# STC11F04E_SOP20_UTo24G.net
KiCad netlist of a schematic drawn in Altium Designer
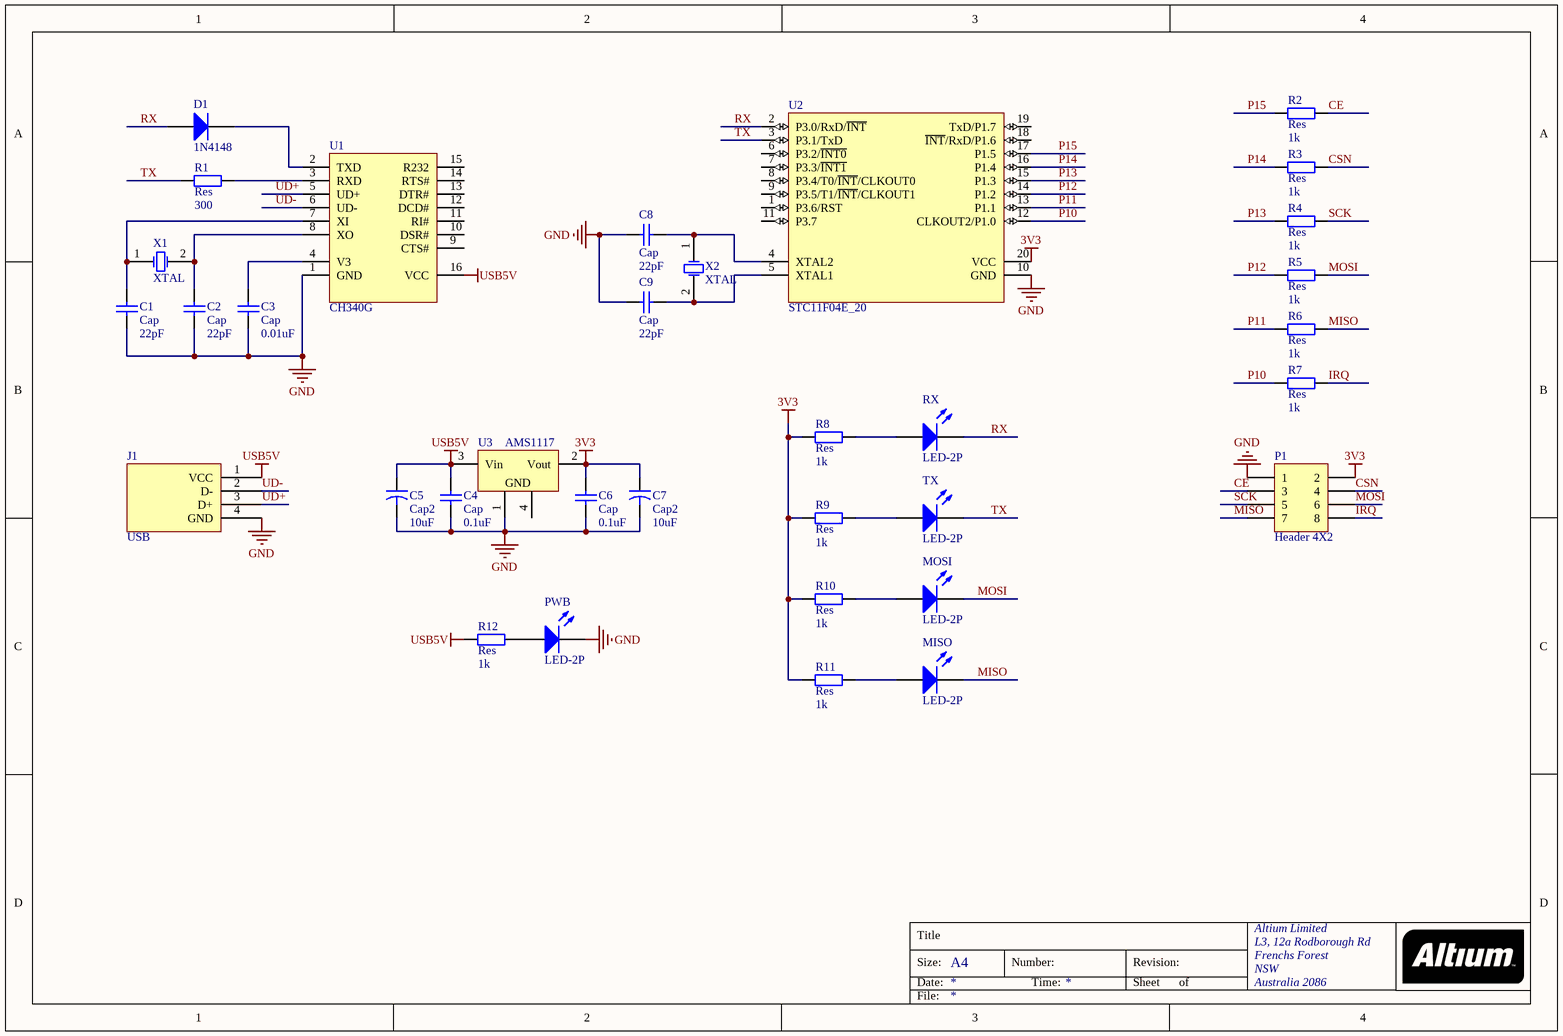
[diagram p0: STC11F04E_SOP20_UTo24G.SchDoc]

(export (version "E")
  (design (tool "Eeschema 10.0.6"))
  (components
    (comp (ref "C1")
      (value "Cap")
      (footprint "C0805")
      (description "Capacitor")
      (fields (field (name "ALTIUM_VALUE") "22pF") (field (name "PUBLISHER") "Altium Limited"))
      (libsource (lib "Devices") (part "Cap"))
    )
    (comp (ref "C2")
      (value "Cap")
      (footprint "C0805")
      (description "Capacitor")
      (fields (field (name "ALTIUM_VALUE") "22pF") (field (name "PUBLISHER") "Altium Limited"))
      (libsource (lib "Devices") (part "Cap"))
    )
    (comp (ref "C3")
      (value "Cap")
      (footprint "C0805")
      (description "Capacitor")
      (fields (field (name "ALTIUM_VALUE") "0.01uF") (field (name "PUBLISHER") "Altium Limited"))
      (libsource (lib "Devices") (part "Cap"))
    )
    (comp (ref "C4")
      (value "Cap")
      (footprint "C0805")
      (description "Capacitor")
      (fields (field (name "ALTIUM_VALUE") "0.1uF") (field (name "PUBLISHER") "Altium Limited"))
      (libsource (lib "Devices") (part "Cap"))
    )
    (comp (ref "C5")
      (value "Cap2")
      (footprint "C1206A")
      (description "Capacitor")
      (fields (field (name "ALTIUM_VALUE") "10uF") (field (name "PUBLISHER") "Altium Limited"))
      (libsource (lib "Devices") (part "Cap2"))
    )
    (comp (ref "C6")
      (value "Cap")
      (footprint "C0805")
      (description "Capacitor")
      (fields (field (name "ALTIUM_VALUE") "0.1uF") (field (name "PUBLISHER") "Altium Limited"))
      (libsource (lib "Devices") (part "Cap"))
    )
    (comp (ref "C7")
      (value "Cap2")
      (footprint "C1206A")
      (description "Capacitor")
      (fields (field (name "ALTIUM_VALUE") "10uF") (field (name "PUBLISHER") "Altium Limited"))
      (libsource (lib "Devices") (part "Cap2"))
    )
    (comp (ref "C8")
      (value "Cap")
      (footprint "C0805")
      (description "Capacitor")
      (fields (field (name "ALTIUM_VALUE") "22pF") (field (name "PUBLISHER") "Altium Limited"))
      (libsource (lib "Devices") (part "Cap"))
    )
    (comp (ref "C9")
      (value "Cap")
      (footprint "C0805")
      (description "Capacitor")
      (fields (field (name "ALTIUM_VALUE") "22pF") (field (name "PUBLISHER") "Altium Limited"))
      (libsource (lib "Devices") (part "Cap"))
    )
    (comp (ref "D1")
      (value "1N4148")
      (footprint "C1206A")
      (description "快速开关二极管")
      (libsource (lib "Devices") (part "1N4148"))
    )
    (comp (ref "J1")
      (value "USB")
      (footprint "USB-A-G")
      (description "USB-B")
      (libsource (lib "Connectors") (part "USB"))
    )
    (comp (ref "MISO")
      (value "LED-2P")
      (footprint "C0805")
      (description "发光二极管")
      (libsource (lib "Devices") (part "LED-2P"))
    )
    (comp (ref "MOSI")
      (value "LED-2P")
      (footprint "C0805")
      (description "发光二极管")
      (libsource (lib "Devices") (part "LED-2P"))
    )
    (comp (ref "P1")
      (value "Header 4X2")
      (footprint "HDR2X4")
      (description "Header, 4-Pin, Dual row")
      (fields (field (name "PUBLISHER") "Altium Limited"))
      (libsource (lib "Connectors") (part "Header 4X2"))
    )
    (comp (ref "PWB")
      (value "LED-2P")
      (footprint "C0805")
      (description "发光二极管")
      (libsource (lib "Devices") (part "LED-2P"))
    )
    (comp (ref "R1")
      (value "Res")
      (footprint "0805")
      (description "Resistor")
      (fields (field (name "ALTIUM_VALUE") "300") (field (name "PUBLISHER") "Altium Limited"))
      (libsource (lib "Devices") (part "Res"))
    )
    (comp (ref "R2")
      (value "Res")
      (footprint "0805")
      (description "Resistor")
      (fields (field (name "ALTIUM_VALUE") "1k") (field (name "PUBLISHER") "Altium Limited"))
      (libsource (lib "Devices") (part "Res"))
    )
    (comp (ref "R3")
      (value "Res")
      (footprint "0805")
      (description "Resistor")
      (fields (field (name "ALTIUM_VALUE") "1k") (field (name "PUBLISHER") "Altium Limited"))
      (libsource (lib "Devices") (part "Res"))
    )
    (comp (ref "R4")
      (value "Res")
      (footprint "0805")
      (description "Resistor")
      (fields (field (name "ALTIUM_VALUE") "1k") (field (name "PUBLISHER") "Altium Limited"))
      (libsource (lib "Devices") (part "Res"))
    )
    (comp (ref "R5")
      (value "Res")
      (footprint "0805")
      (description "Resistor")
      (fields (field (name "ALTIUM_VALUE") "1k") (field (name "PUBLISHER") "Altium Limited"))
      (libsource (lib "Devices") (part "Res"))
    )
    (comp (ref "R6")
      (value "Res")
      (footprint "0805")
      (description "Resistor")
      (fields (field (name "ALTIUM_VALUE") "1k") (field (name "PUBLISHER") "Altium Limited"))
      (libsource (lib "Devices") (part "Res"))
    )
    (comp (ref "R7")
      (value "Res")
      (footprint "0805")
      (description "Resistor")
      (fields (field (name "ALTIUM_VALUE") "1k") (field (name "PUBLISHER") "Altium Limited"))
      (libsource (lib "Devices") (part "Res"))
    )
    (comp (ref "R8")
      (value "Res")
      (footprint "0805")
      (description "Resistor")
      (fields (field (name "ALTIUM_VALUE") "1k") (field (name "PUBLISHER") "Altium Limited"))
      (libsource (lib "Devices") (part "Res"))
    )
    (comp (ref "R9")
      (value "Res")
      (footprint "0805")
      (description "Resistor")
      (fields (field (name "ALTIUM_VALUE") "1k") (field (name "PUBLISHER") "Altium Limited"))
      (libsource (lib "Devices") (part "Res"))
    )
    (comp (ref "R10")
      (value "Res")
      (footprint "0805")
      (description "Resistor")
      (fields (field (name "ALTIUM_VALUE") "1k") (field (name "PUBLISHER") "Altium Limited"))
      (libsource (lib "Devices") (part "Res"))
    )
    (comp (ref "R11")
      (value "Res")
      (footprint "0805")
      (description "Resistor")
      (fields (field (name "ALTIUM_VALUE") "1k") (field (name "PUBLISHER") "Altium Limited"))
      (libsource (lib "Devices") (part "Res"))
    )
    (comp (ref "R12")
      (value "Res")
      (footprint "0805")
      (description "Resistor")
      (fields (field (name "ALTIUM_VALUE") "1k") (field (name "PUBLISHER") "Altium Limited"))
      (libsource (lib "Devices") (part "Res"))
    )
    (comp (ref "RX")
      (value "LED-2P")
      (footprint "C0805")
      (description "发光二极管")
      (libsource (lib "Devices") (part "LED-2P"))
    )
    (comp (ref "TX")
      (value "LED-2P")
      (footprint "C0805")
      (description "发光二极管")
      (libsource (lib "Devices") (part "LED-2P"))
    )
    (comp (ref "U1")
      (value "CH340G")
      (footprint "SOP16")
      (description "USB 总线转接芯片")
      (libsource (lib "IC") (part "CH340G"))
    )
    (comp (ref "U2")
      (value "STC11F04E_20")
      (footprint "SOP20")
      (description "增强型8051单片机")
      (libsource (lib "STC") (part "STC11F04E_20"))
    )
    (comp (ref "U3")
      (value "AMS1117")
      (footprint "SOT-223")
      (description "低压稳压器-1A")
      (libsource (lib "IC") (part "AMS1117"))
    )
    (comp (ref "X1")
      (value "XTAL")
      (footprint "XTAL1")
      (description "Crystal Oscillator")
      (fields (field (name "PUBLISHER") "Altium Limited"))
      (libsource (lib "Miscellaneous Devices") (part "XTAL"))
    )
    (comp (ref "X2")
      (value "XTAL")
      (footprint "XTAL1")
      (description "Crystal Oscillator")
      (fields (field (name "PUBLISHER") "Altium Limited"))
      (libsource (lib "Miscellaneous Devices") (part "XTAL"))
    )
  )
  (nets
    (net (code "1") (name "/CE") (class "Default")
      (node (ref "P1") (pin "3") (pinfunction "3_3") (pintype "passive"))
      (node (ref "R2") (pin "2") (pinfunction "2_2") (pintype "passive"))
    )
    (net (code "2") (name "/CSN") (class "Default")
      (node (ref "P1") (pin "4") (pinfunction "4_4") (pintype "passive"))
      (node (ref "R3") (pin "2") (pinfunction "2_2") (pintype "passive"))
    )
    (net (code "3") (name "/IRQ") (class "Default")
      (node (ref "P1") (pin "8") (pinfunction "8_8") (pintype "passive"))
      (node (ref "R7") (pin "2") (pinfunction "2_2") (pintype "passive"))
    )
    (net (code "4") (name "/MISO") (class "Default")
      (node (ref "MISO") (pin "2") (pinfunction "K_2") (pintype "passive"))
      (node (ref "P1") (pin "7") (pinfunction "7_7") (pintype "passive"))
      (node (ref "R6") (pin "2") (pinfunction "2_2") (pintype "passive"))
    )
    (net (code "5") (name "/MOSI") (class "Default")
      (node (ref "MOSI") (pin "2") (pinfunction "K_2") (pintype "passive"))
      (node (ref "P1") (pin "6") (pinfunction "6_6") (pintype "passive"))
      (node (ref "R5") (pin "2") (pinfunction "2_2") (pintype "passive"))
    )
    (net (code "6") (name "/P10") (class "Default")
      (node (ref "R7") (pin "1") (pinfunction "1_1") (pintype "passive"))
      (node (ref "U2") (pin "12") (pinfunction "CLKOUT2/P1.0_12") (pintype "bidirectional"))
    )
    (net (code "7") (name "/P11") (class "Default")
      (node (ref "R6") (pin "1") (pinfunction "1_1") (pintype "passive"))
      (node (ref "U2") (pin "13") (pinfunction "P1.1_13") (pintype "bidirectional"))
    )
    (net (code "8") (name "/P12") (class "Default")
      (node (ref "R5") (pin "1") (pinfunction "1_1") (pintype "passive"))
      (node (ref "U2") (pin "14") (pinfunction "P1.2_14") (pintype "bidirectional"))
    )
    (net (code "9") (name "/P13") (class "Default")
      (node (ref "R4") (pin "1") (pinfunction "1_1") (pintype "passive"))
      (node (ref "U2") (pin "15") (pinfunction "P1.3_15") (pintype "bidirectional"))
    )
    (net (code "10") (name "/P14") (class "Default")
      (node (ref "R3") (pin "1") (pinfunction "1_1") (pintype "passive"))
      (node (ref "U2") (pin "16") (pinfunction "P1.4_16") (pintype "bidirectional"))
    )
    (net (code "11") (name "/P15") (class "Default")
      (node (ref "R2") (pin "1") (pinfunction "1_1") (pintype "passive"))
      (node (ref "U2") (pin "17") (pinfunction "P1.5_17") (pintype "bidirectional"))
    )
    (net (code "12") (name "/RX") (class "Default")
      (node (ref "D1") (pin "1") (pinfunction "A_1") (pintype "passive"))
      (node (ref "RX") (pin "2") (pinfunction "K_2") (pintype "passive"))
      (node (ref "U2") (pin "2") (pinfunction "P3.0/RxD/~{INT}_2") (pintype "bidirectional"))
    )
    (net (code "13") (name "/SCK") (class "Default")
      (node (ref "P1") (pin "5") (pinfunction "5_5") (pintype "passive"))
      (node (ref "R4") (pin "2") (pinfunction "2_2") (pintype "passive"))
    )
    (net (code "14") (name "/TX") (class "Default")
      (node (ref "R1") (pin "1") (pinfunction "1_1") (pintype "passive"))
      (node (ref "TX") (pin "2") (pinfunction "K_2") (pintype "passive"))
      (node (ref "U2") (pin "3") (pinfunction "P3.1/TxD_3") (pintype "bidirectional"))
    )
    (net (code "15") (name "/UD+") (class "Default")
      (node (ref "J1") (pin "3") (pinfunction "D+_3") (pintype "passive"))
      (node (ref "U1") (pin "5") (pinfunction "UD+_5") (pintype "passive"))
    )
    (net (code "16") (name "/UD-") (class "Default")
      (node (ref "J1") (pin "2") (pinfunction "D-_2") (pintype "passive"))
      (node (ref "U1") (pin "6") (pinfunction "UD-_6") (pintype "passive"))
    )
    (net (code "17") (name "3V3") (class "Default")
      (node (ref "C6") (pin "2") (pinfunction "2_2") (pintype "passive"))
      (node (ref "C7") (pin "1") (pinfunction "1_1") (pintype "passive"))
      (node (ref "P1") (pin "2") (pinfunction "2_2") (pintype "passive"))
      (node (ref "R10") (pin "1") (pinfunction "1_1") (pintype "passive"))
      (node (ref "R11") (pin "1") (pinfunction "1_1") (pintype "passive"))
      (node (ref "R8") (pin "1") (pinfunction "1_1") (pintype "passive"))
      (node (ref "R9") (pin "1") (pinfunction "1_1") (pintype "passive"))
      (node (ref "U2") (pin "20") (pinfunction "VCC_20") (pintype "power_in"))
      (node (ref "U3") (pin "2") (pinfunction "Vout_2") (pintype "passive"))
    )
    (net (code "18") (name "GND") (class "Default")
      (node (ref "C1") (pin "2") (pinfunction "2_2") (pintype "passive"))
      (node (ref "C2") (pin "2") (pinfunction "2_2") (pintype "passive"))
      (node (ref "C3") (pin "1") (pinfunction "1_1") (pintype "passive"))
      (node (ref "C4") (pin "1") (pinfunction "1_1") (pintype "passive"))
      (node (ref "C5") (pin "2") (pinfunction "2_2") (pintype "passive"))
      (node (ref "C6") (pin "1") (pinfunction "1_1") (pintype "passive"))
      (node (ref "C7") (pin "2") (pinfunction "2_2") (pintype "passive"))
      (node (ref "C8") (pin "2") (pinfunction "2_2") (pintype "passive"))
      (node (ref "C9") (pin "2") (pinfunction "2_2") (pintype "passive"))
      (node (ref "J1") (pin "4") (pinfunction "GND_4") (pintype "passive"))
      (node (ref "P1") (pin "1") (pinfunction "1_1") (pintype "passive"))
      (node (ref "PWB") (pin "2") (pinfunction "K_2") (pintype "passive"))
      (node (ref "U1") (pin "1") (pinfunction "GND_1") (pintype "power_in"))
      (node (ref "U2") (pin "10") (pinfunction "GND_10") (pintype "power_in"))
      (node (ref "U3") (pin "1") (pinfunction "GND_1") (pintype "passive"))
    )
    (net (code "19") (name "Net-(D1-K)") (class "Default")
      (node (ref "D1") (pin "2") (pinfunction "K_2") (pintype "passive"))
      (node (ref "U1") (pin "2") (pinfunction "TXD_2") (pintype "passive"))
    )
    (net (code "20") (name "Net-(MISO-A)") (class "Default")
      (node (ref "MISO") (pin "1") (pinfunction "A_1") (pintype "passive"))
      (node (ref "R11") (pin "2") (pinfunction "2_2") (pintype "passive"))
    )
    (net (code "21") (name "Net-(MOSI-A)") (class "Default")
      (node (ref "MOSI") (pin "1") (pinfunction "A_1") (pintype "passive"))
      (node (ref "R10") (pin "2") (pinfunction "2_2") (pintype "passive"))
    )
    (net (code "22") (name "Net-(PWB-A)") (class "Default")
      (node (ref "PWB") (pin "1") (pinfunction "A_1") (pintype "passive"))
      (node (ref "R12") (pin "2") (pinfunction "2_2") (pintype "passive"))
    )
    (net (code "23") (name "Net-(RX-A)") (class "Default")
      (node (ref "R8") (pin "2") (pinfunction "2_2") (pintype "passive"))
      (node (ref "RX") (pin "1") (pinfunction "A_1") (pintype "passive"))
    )
    (net (code "24") (name "Net-(TX-A)") (class "Default")
      (node (ref "R9") (pin "2") (pinfunction "2_2") (pintype "passive"))
      (node (ref "TX") (pin "1") (pinfunction "A_1") (pintype "passive"))
    )
    (net (code "25") (name "Net-(U1-RXD)") (class "Default")
      (node (ref "R1") (pin "2") (pinfunction "2_2") (pintype "passive"))
      (node (ref "U1") (pin "3") (pinfunction "RXD_3") (pintype "passive"))
    )
    (net (code "26") (name "Net-(U1-V3)") (class "Default")
      (node (ref "C3") (pin "2") (pinfunction "2_2") (pintype "passive"))
      (node (ref "U1") (pin "4") (pinfunction "V3_4") (pintype "passive"))
    )
    (net (code "27") (name "Net-(U1-XI)") (class "Default")
      (node (ref "C1") (pin "1") (pinfunction "1_1") (pintype "passive"))
      (node (ref "U1") (pin "7") (pinfunction "XI_7") (pintype "passive"))
      (node (ref "X1") (pin "1") (pinfunction "OSC1_1") (pintype "passive"))
    )
    (net (code "28") (name "Net-(U1-XO)") (class "Default")
      (node (ref "C2") (pin "1") (pinfunction "1_1") (pintype "passive"))
      (node (ref "U1") (pin "8") (pinfunction "XO_8") (pintype "passive"))
      (node (ref "X1") (pin "2") (pinfunction "OSC2_2") (pintype "passive"))
    )
    (net (code "29") (name "Net-(U2-XTAL1)") (class "Default")
      (node (ref "C9") (pin "1") (pinfunction "1_1") (pintype "passive"))
      (node (ref "U2") (pin "5") (pinfunction "XTAL1_5") (pintype "passive"))
      (node (ref "X2") (pin "2") (pinfunction "OSC2_2") (pintype "passive"))
    )
    (net (code "30") (name "Net-(U2-XTAL2)") (class "Default")
      (node (ref "C8") (pin "1") (pinfunction "1_1") (pintype "passive"))
      (node (ref "U2") (pin "4") (pinfunction "XTAL2_4") (pintype "passive"))
      (node (ref "X2") (pin "1") (pinfunction "OSC1_1") (pintype "passive"))
    )
    (net (code "31") (name "USB5V") (class "Default")
      (node (ref "C4") (pin "2") (pinfunction "2_2") (pintype "passive"))
      (node (ref "C5") (pin "1") (pinfunction "1_1") (pintype "passive"))
      (node (ref "J1") (pin "1") (pinfunction "VCC_1") (pintype "passive"))
      (node (ref "R12") (pin "1") (pinfunction "1_1") (pintype "passive"))
      (node (ref "U1") (pin "16") (pinfunction "VCC_16") (pintype "power_in"))
      (node (ref "U3") (pin "3") (pinfunction "Vin_3") (pintype "passive"))
    )
    (net (code "32") (name "unconnected-(U1-CTS#-Pad9)") (class "Default")
      (node (ref "U1") (pin "9") (pinfunction "CTS#_9") (pintype "passive"))
    )
    (net (code "33") (name "unconnected-(U1-DCD#-Pad12)") (class "Default")
      (node (ref "U1") (pin "12") (pinfunction "DCD#_12") (pintype "passive"))
    )
    (net (code "34") (name "unconnected-(U1-DSR#-Pad10)") (class "Default")
      (node (ref "U1") (pin "10") (pinfunction "DSR#_10") (pintype "passive"))
    )
    (net (code "35") (name "unconnected-(U1-DTR#-Pad13)") (class "Default")
      (node (ref "U1") (pin "13") (pinfunction "DTR#_13") (pintype "passive"))
    )
    (net (code "36") (name "unconnected-(U1-R232-Pad15)") (class "Default")
      (node (ref "U1") (pin "15") (pinfunction "R232_15") (pintype "passive"))
    )
    (net (code "37") (name "unconnected-(U1-RI#-Pad11)") (class "Default")
      (node (ref "U1") (pin "11") (pinfunction "RI#_11") (pintype "passive"))
    )
    (net (code "38") (name "unconnected-(U1-RTS#-Pad14)") (class "Default")
      (node (ref "U1") (pin "14") (pinfunction "RTS#_14") (pintype "passive"))
    )
    (net (code "39") (name "unconnected-(U2-P3.2{slash}~{INT0}-Pad6)") (class "Default")
      (node (ref "U2") (pin "6") (pinfunction "P3.2/~{INT0}_6") (pintype "bidirectional"))
    )
    (net (code "40") (name "unconnected-(U2-P3.3{slash}~{INT1}-Pad7)") (class "Default")
      (node (ref "U2") (pin "7") (pinfunction "P3.3/~{INT1}_7") (pintype "bidirectional"))
    )
    (net (code "41") (name "unconnected-(U2-P3.4{slash}T0{slash}~{INT}{slash}CLKOUT0-Pad8)") (class "Default")
      (node (ref "U2") (pin "8") (pinfunction "P3.4/T0/~{INT}/CLKOUT0_8") (pintype "bidirectional"))
    )
    (net (code "42") (name "unconnected-(U2-P3.5{slash}T1{slash}~{INT}{slash}CLKOUT1-Pad9)") (class "Default")
      (node (ref "U2") (pin "9") (pinfunction "P3.5/T1/~{INT}/CLKOUT1_9") (pintype "bidirectional"))
    )
    (net (code "43") (name "unconnected-(U2-P3.6{slash}RST-Pad1)") (class "Default")
      (node (ref "U2") (pin "1") (pinfunction "P3.6/RST_1") (pintype "bidirectional"))
    )
    (net (code "44") (name "unconnected-(U2-P3.7-Pad11)") (class "Default")
      (node (ref "U2") (pin "11") (pinfunction "P3.7_11") (pintype "bidirectional"))
    )
    (net (code "45") (name "unconnected-(U2-TxD{slash}P1.7-Pad19)") (class "Default")
      (node (ref "U2") (pin "19") (pinfunction "TxD/P1.7_19") (pintype "bidirectional"))
    )
    (net (code "46") (name "unconnected-(U2-~{INT}{slash}RxD{slash}P1.6-Pad18)") (class "Default")
      (node (ref "U2") (pin "18") (pinfunction "~{INT}/RxD/P1.6_18") (pintype "bidirectional"))
    )
    (net (code "47") (name "unconnected-(U3-GND-Pad4)") (class "Default")
      (node (ref "U3") (pin "4") (pinfunction "GND_4") (pintype "passive"))
    )
  )
)
